# light.net
KiCad netlist of a schematic drawn in EAGLE
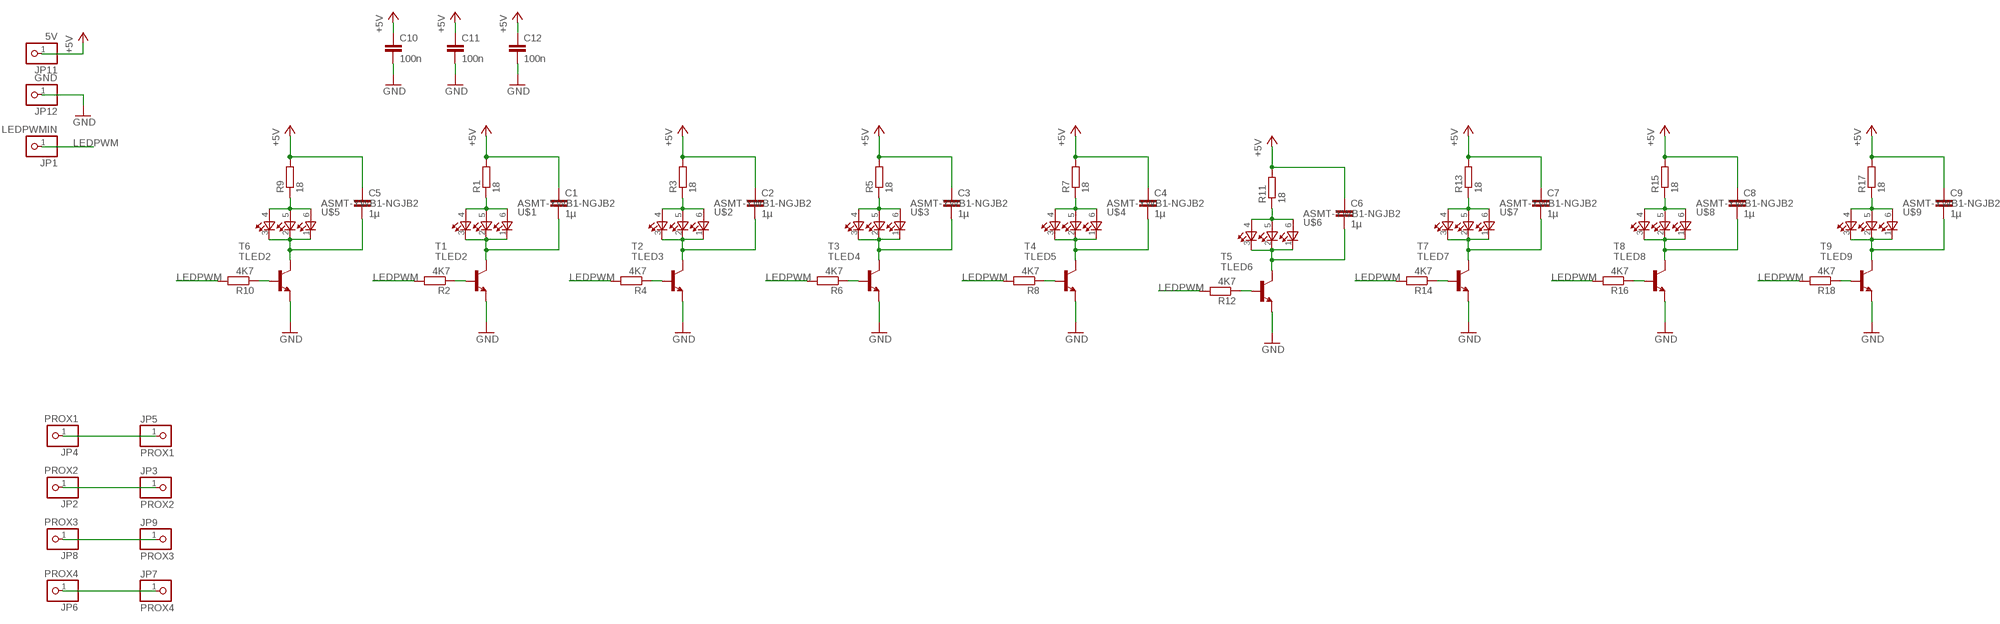
[diagram p0: schematic, sheet 1]

(export (version "E")
  (design (tool "Eeschema 10.0.6"))
  (components
    (comp (ref "C1")
      (value "1µ")
      (footprint "eagle-import:C0805")
      (libsource (lib "eagle-import") (part "C-EUC0805"))
    )
    (comp (ref "C2")
      (value "1µ")
      (footprint "eagle-import:C0805")
      (libsource (lib "eagle-import") (part "C-EUC0805"))
    )
    (comp (ref "C3")
      (value "1µ")
      (footprint "eagle-import:C0805")
      (libsource (lib "eagle-import") (part "C-EUC0805"))
    )
    (comp (ref "C4")
      (value "1µ")
      (footprint "eagle-import:C0805")
      (libsource (lib "eagle-import") (part "C-EUC0805"))
    )
    (comp (ref "C5")
      (value "1µ")
      (footprint "eagle-import:C0805")
      (libsource (lib "eagle-import") (part "C-EUC0805"))
    )
    (comp (ref "C6")
      (value "1µ")
      (footprint "eagle-import:C0805")
      (libsource (lib "eagle-import") (part "C-EUC0805"))
    )
    (comp (ref "C7")
      (value "1µ")
      (footprint "eagle-import:C0805")
      (libsource (lib "eagle-import") (part "C-EUC0805"))
    )
    (comp (ref "C8")
      (value "1µ")
      (footprint "eagle-import:C0805")
      (libsource (lib "eagle-import") (part "C-EUC0805"))
    )
    (comp (ref "C9")
      (value "1µ")
      (footprint "eagle-import:C0805")
      (libsource (lib "eagle-import") (part "C-EUC0805"))
    )
    (comp (ref "C10")
      (value "100n")
      (footprint "eagle-import:C0805")
      (libsource (lib "eagle-import") (part "C-EUC0805"))
    )
    (comp (ref "C11")
      (value "100n")
      (footprint "eagle-import:C0805")
      (libsource (lib "eagle-import") (part "C-EUC0805"))
    )
    (comp (ref "C12")
      (value "100n")
      (footprint "eagle-import:C0805")
      (libsource (lib "eagle-import") (part "C-EUC0805"))
    )
    (comp (ref "JP1")
      (value "LEDPWMIN")
      (footprint "eagle-import:1X01")
      (libsource (lib "eagle-import") (part "PINHD-1X1"))
    )
    (comp (ref "JP2")
      (value "PROX2")
      (footprint "eagle-import:1X01")
      (libsource (lib "eagle-import") (part "PINHD-1X1"))
    )
    (comp (ref "JP3")
      (value "PROX2")
      (footprint "eagle-import:1X01")
      (libsource (lib "eagle-import") (part "PINHD-1X1"))
    )
    (comp (ref "JP4")
      (value "PROX1")
      (footprint "eagle-import:1X01")
      (libsource (lib "eagle-import") (part "PINHD-1X1"))
    )
    (comp (ref "JP5")
      (value "PROX1")
      (footprint "eagle-import:1X01")
      (libsource (lib "eagle-import") (part "PINHD-1X1"))
    )
    (comp (ref "JP6")
      (value "PROX4")
      (footprint "eagle-import:1X01")
      (libsource (lib "eagle-import") (part "PINHD-1X1"))
    )
    (comp (ref "JP7")
      (value "PROX4")
      (footprint "eagle-import:1X01")
      (libsource (lib "eagle-import") (part "PINHD-1X1"))
    )
    (comp (ref "JP8")
      (value "PROX3")
      (footprint "eagle-import:1X01")
      (libsource (lib "eagle-import") (part "PINHD-1X1"))
    )
    (comp (ref "JP9")
      (value "PROX3")
      (footprint "eagle-import:1X01")
      (libsource (lib "eagle-import") (part "PINHD-1X1"))
    )
    (comp (ref "JP11")
      (value "5V")
      (footprint "eagle-import:1X01")
      (libsource (lib "eagle-import") (part "PINHD-1X1"))
    )
    (comp (ref "JP12")
      (value "GND")
      (footprint "eagle-import:1X01")
      (libsource (lib "eagle-import") (part "PINHD-1X1"))
    )
    (comp (ref "R1")
      (value "18")
      (footprint "eagle-import:R0805")
      (libsource (lib "eagle-import") (part "R-EU_R0805"))
    )
    (comp (ref "R2")
      (value "4K7")
      (footprint "eagle-import:R0805")
      (libsource (lib "eagle-import") (part "R-EU_R0805"))
    )
    (comp (ref "R3")
      (value "18")
      (footprint "eagle-import:R0805")
      (libsource (lib "eagle-import") (part "R-EU_R0805"))
    )
    (comp (ref "R4")
      (value "4K7")
      (footprint "eagle-import:R0805")
      (libsource (lib "eagle-import") (part "R-EU_R0805"))
    )
    (comp (ref "R5")
      (value "18")
      (footprint "eagle-import:R0805")
      (libsource (lib "eagle-import") (part "R-EU_R0805"))
    )
    (comp (ref "R6")
      (value "4K7")
      (footprint "eagle-import:R0805")
      (libsource (lib "eagle-import") (part "R-EU_R0805"))
    )
    (comp (ref "R7")
      (value "18")
      (footprint "eagle-import:R0805")
      (libsource (lib "eagle-import") (part "R-EU_R0805"))
    )
    (comp (ref "R8")
      (value "4K7")
      (footprint "eagle-import:R0805")
      (libsource (lib "eagle-import") (part "R-EU_R0805"))
    )
    (comp (ref "R9")
      (value "18")
      (footprint "eagle-import:R0805")
      (libsource (lib "eagle-import") (part "R-EU_R0805"))
    )
    (comp (ref "R10")
      (value "4K7")
      (footprint "eagle-import:R0805")
      (libsource (lib "eagle-import") (part "R-EU_R0805"))
    )
    (comp (ref "R11")
      (value "18")
      (footprint "eagle-import:R0805")
      (libsource (lib "eagle-import") (part "R-EU_R0805"))
    )
    (comp (ref "R12")
      (value "4K7")
      (footprint "eagle-import:R0805")
      (libsource (lib "eagle-import") (part "R-EU_R0805"))
    )
    (comp (ref "R13")
      (value "18")
      (footprint "eagle-import:R0805")
      (libsource (lib "eagle-import") (part "R-EU_R0805"))
    )
    (comp (ref "R14")
      (value "4K7")
      (footprint "eagle-import:R0805")
      (libsource (lib "eagle-import") (part "R-EU_R0805"))
    )
    (comp (ref "R15")
      (value "18")
      (footprint "eagle-import:R0805")
      (libsource (lib "eagle-import") (part "R-EU_R0805"))
    )
    (comp (ref "R16")
      (value "4K7")
      (footprint "eagle-import:R0805")
      (libsource (lib "eagle-import") (part "R-EU_R0805"))
    )
    (comp (ref "R17")
      (value "18")
      (footprint "eagle-import:R0805")
      (libsource (lib "eagle-import") (part "R-EU_R0805"))
    )
    (comp (ref "R18")
      (value "4K7")
      (footprint "eagle-import:R0805")
      (libsource (lib "eagle-import") (part "R-EU_R0805"))
    )
    (comp (ref "T1")
      (value "TLED2")
      (footprint "eagle-import:SOT23-BEC")
      (libsource (lib "eagle-import") (part "-NPN-SOT23-BECMMBT3904LT1"))
    )
    (comp (ref "T2")
      (value "TLED3")
      (footprint "eagle-import:SOT23-BEC")
      (libsource (lib "eagle-import") (part "-NPN-SOT23-BECMMBT3904LT1"))
    )
    (comp (ref "T3")
      (value "TLED4")
      (footprint "eagle-import:SOT23-BEC")
      (libsource (lib "eagle-import") (part "-NPN-SOT23-BECMMBT3904LT1"))
    )
    (comp (ref "T4")
      (value "TLED5")
      (footprint "eagle-import:SOT23-BEC")
      (libsource (lib "eagle-import") (part "-NPN-SOT23-BECMMBT3904LT1"))
    )
    (comp (ref "T5")
      (value "TLED6")
      (footprint "eagle-import:SOT23-BEC")
      (libsource (lib "eagle-import") (part "-NPN-SOT23-BECMMBT3904LT1"))
    )
    (comp (ref "T6")
      (value "TLED2")
      (footprint "eagle-import:SOT23-BEC")
      (libsource (lib "eagle-import") (part "-NPN-SOT23-BECMMBT3904LT1"))
    )
    (comp (ref "T7")
      (value "TLED7")
      (footprint "eagle-import:SOT23-BEC")
      (libsource (lib "eagle-import") (part "-NPN-SOT23-BECMMBT3904LT1"))
    )
    (comp (ref "T8")
      (value "TLED8")
      (footprint "eagle-import:SOT23-BEC")
      (libsource (lib "eagle-import") (part "-NPN-SOT23-BECMMBT3904LT1"))
    )
    (comp (ref "T9")
      (value "TLED9")
      (footprint "eagle-import:SOT23-BEC")
      (libsource (lib "eagle-import") (part "-NPN-SOT23-BECMMBT3904LT1"))
    )
    (comp (ref "U$1")
      (value "ASMT-YWB1-NGJB2")
      (footprint "eagle-import:ASMT-YWB1-NGJB2")
      (libsource (lib "eagle-import") (part "ASMT-YWB1-NGJB2"))
    )
    (comp (ref "U$2")
      (value "ASMT-YWB1-NGJB2")
      (footprint "eagle-import:ASMT-YWB1-NGJB2")
      (libsource (lib "eagle-import") (part "ASMT-YWB1-NGJB2"))
    )
    (comp (ref "U$3")
      (value "ASMT-YWB1-NGJB2")
      (footprint "eagle-import:ASMT-YWB1-NGJB2")
      (libsource (lib "eagle-import") (part "ASMT-YWB1-NGJB2"))
    )
    (comp (ref "U$4")
      (value "ASMT-YWB1-NGJB2")
      (footprint "eagle-import:ASMT-YWB1-NGJB2")
      (libsource (lib "eagle-import") (part "ASMT-YWB1-NGJB2"))
    )
    (comp (ref "U$5")
      (value "ASMT-YWB1-NGJB2")
      (footprint "eagle-import:ASMT-YWB1-NGJB2")
      (libsource (lib "eagle-import") (part "ASMT-YWB1-NGJB2"))
    )
    (comp (ref "U$6")
      (value "ASMT-YWB1-NGJB2")
      (footprint "eagle-import:ASMT-YWB1-NGJB2")
      (libsource (lib "eagle-import") (part "ASMT-YWB1-NGJB2"))
    )
    (comp (ref "U$7")
      (value "ASMT-YWB1-NGJB2")
      (footprint "eagle-import:ASMT-YWB1-NGJB2")
      (libsource (lib "eagle-import") (part "ASMT-YWB1-NGJB2"))
    )
    (comp (ref "U$8")
      (value "ASMT-YWB1-NGJB2")
      (footprint "eagle-import:ASMT-YWB1-NGJB2")
      (libsource (lib "eagle-import") (part "ASMT-YWB1-NGJB2"))
    )
    (comp (ref "U$9")
      (value "ASMT-YWB1-NGJB2")
      (footprint "eagle-import:ASMT-YWB1-NGJB2")
      (libsource (lib "eagle-import") (part "ASMT-YWB1-NGJB2"))
    )
  )
  (nets
    (net (code "1") (name "+5V") (class "Default")
      (node (ref "C1") (pin "1") (pinfunction "1_1") (pintype "passive"))
      (node (ref "C10") (pin "1") (pinfunction "1_1") (pintype "passive"))
      (node (ref "C11") (pin "1") (pinfunction "1_1") (pintype "passive"))
      (node (ref "C12") (pin "1") (pinfunction "1_1") (pintype "passive"))
      (node (ref "C2") (pin "1") (pinfunction "1_1") (pintype "passive"))
      (node (ref "C3") (pin "1") (pinfunction "1_1") (pintype "passive"))
      (node (ref "C4") (pin "1") (pinfunction "1_1") (pintype "passive"))
      (node (ref "C5") (pin "1") (pinfunction "1_1") (pintype "passive"))
      (node (ref "C6") (pin "1") (pinfunction "1_1") (pintype "passive"))
      (node (ref "C7") (pin "1") (pinfunction "1_1") (pintype "passive"))
      (node (ref "C8") (pin "1") (pinfunction "1_1") (pintype "passive"))
      (node (ref "C9") (pin "1") (pinfunction "1_1") (pintype "passive"))
      (node (ref "JP11") (pin "1") (pinfunction "1_1") (pintype "passive"))
      (node (ref "R1") (pin "2") (pinfunction "2_2") (pintype "passive"))
      (node (ref "R11") (pin "2") (pinfunction "2_2") (pintype "passive"))
      (node (ref "R13") (pin "2") (pinfunction "2_2") (pintype "passive"))
      (node (ref "R15") (pin "2") (pinfunction "2_2") (pintype "passive"))
      (node (ref "R17") (pin "2") (pinfunction "2_2") (pintype "passive"))
      (node (ref "R3") (pin "2") (pinfunction "2_2") (pintype "passive"))
      (node (ref "R5") (pin "2") (pinfunction "2_2") (pintype "passive"))
      (node (ref "R7") (pin "2") (pinfunction "2_2") (pintype "passive"))
      (node (ref "R9") (pin "2") (pinfunction "2_2") (pintype "passive"))
    )
    (net (code "2") (name "/LEDPWM") (class "Default")
      (node (ref "JP1") (pin "1") (pinfunction "1_1") (pintype "passive"))
      (node (ref "R10") (pin "2") (pinfunction "2_2") (pintype "passive"))
      (node (ref "R12") (pin "2") (pinfunction "2_2") (pintype "passive"))
      (node (ref "R14") (pin "2") (pinfunction "2_2") (pintype "passive"))
      (node (ref "R16") (pin "2") (pinfunction "2_2") (pintype "passive"))
      (node (ref "R18") (pin "2") (pinfunction "2_2") (pintype "passive"))
      (node (ref "R2") (pin "2") (pinfunction "2_2") (pintype "passive"))
      (node (ref "R4") (pin "2") (pinfunction "2_2") (pintype "passive"))
      (node (ref "R6") (pin "2") (pinfunction "2_2") (pintype "passive"))
      (node (ref "R8") (pin "2") (pinfunction "2_2") (pintype "passive"))
    )
    (net (code "3") (name "GND") (class "Default")
      (node (ref "C10") (pin "2") (pinfunction "2_2") (pintype "passive"))
      (node (ref "C11") (pin "2") (pinfunction "2_2") (pintype "passive"))
      (node (ref "C12") (pin "2") (pinfunction "2_2") (pintype "passive"))
      (node (ref "JP12") (pin "1") (pinfunction "1_1") (pintype "passive"))
      (node (ref "T1") (pin "E") (pinfunction "E_E") (pintype "passive"))
      (node (ref "T2") (pin "E") (pinfunction "E_E") (pintype "passive"))
      (node (ref "T3") (pin "E") (pinfunction "E_E") (pintype "passive"))
      (node (ref "T4") (pin "E") (pinfunction "E_E") (pintype "passive"))
      (node (ref "T5") (pin "E") (pinfunction "E_E") (pintype "passive"))
      (node (ref "T6") (pin "E") (pinfunction "E_E") (pintype "passive"))
      (node (ref "T7") (pin "E") (pinfunction "E_E") (pintype "passive"))
      (node (ref "T8") (pin "E") (pinfunction "E_E") (pintype "passive"))
      (node (ref "T9") (pin "E") (pinfunction "E_E") (pintype "passive"))
    )
    (net (code "4") (name "Net-(C1-Pad2)") (class "Default")
      (node (ref "C1") (pin "2") (pinfunction "2_2") (pintype "passive"))
      (node (ref "T1") (pin "C") (pinfunction "C_C") (pintype "passive"))
      (node (ref "U$1") (pin "1") (pinfunction "1_1") (pintype "passive"))
      (node (ref "U$1") (pin "2") (pinfunction "2_2") (pintype "passive"))
      (node (ref "U$1") (pin "3") (pinfunction "3_3") (pintype "passive"))
    )
    (net (code "5") (name "Net-(C2-Pad2)") (class "Default")
      (node (ref "C2") (pin "2") (pinfunction "2_2") (pintype "passive"))
      (node (ref "T2") (pin "C") (pinfunction "C_C") (pintype "passive"))
      (node (ref "U$2") (pin "1") (pinfunction "1_1") (pintype "passive"))
      (node (ref "U$2") (pin "2") (pinfunction "2_2") (pintype "passive"))
      (node (ref "U$2") (pin "3") (pinfunction "3_3") (pintype "passive"))
    )
    (net (code "6") (name "Net-(C3-Pad2)") (class "Default")
      (node (ref "C3") (pin "2") (pinfunction "2_2") (pintype "passive"))
      (node (ref "T3") (pin "C") (pinfunction "C_C") (pintype "passive"))
      (node (ref "U$3") (pin "1") (pinfunction "1_1") (pintype "passive"))
      (node (ref "U$3") (pin "2") (pinfunction "2_2") (pintype "passive"))
      (node (ref "U$3") (pin "3") (pinfunction "3_3") (pintype "passive"))
    )
    (net (code "7") (name "Net-(C4-Pad2)") (class "Default")
      (node (ref "C4") (pin "2") (pinfunction "2_2") (pintype "passive"))
      (node (ref "T4") (pin "C") (pinfunction "C_C") (pintype "passive"))
      (node (ref "U$4") (pin "1") (pinfunction "1_1") (pintype "passive"))
      (node (ref "U$4") (pin "2") (pinfunction "2_2") (pintype "passive"))
      (node (ref "U$4") (pin "3") (pinfunction "3_3") (pintype "passive"))
    )
    (net (code "8") (name "Net-(C5-Pad2)") (class "Default")
      (node (ref "C5") (pin "2") (pinfunction "2_2") (pintype "passive"))
      (node (ref "T6") (pin "C") (pinfunction "C_C") (pintype "passive"))
      (node (ref "U$5") (pin "1") (pinfunction "1_1") (pintype "passive"))
      (node (ref "U$5") (pin "2") (pinfunction "2_2") (pintype "passive"))
      (node (ref "U$5") (pin "3") (pinfunction "3_3") (pintype "passive"))
    )
    (net (code "9") (name "Net-(C6-Pad2)") (class "Default")
      (node (ref "C6") (pin "2") (pinfunction "2_2") (pintype "passive"))
      (node (ref "T5") (pin "C") (pinfunction "C_C") (pintype "passive"))
      (node (ref "U$6") (pin "1") (pinfunction "1_1") (pintype "passive"))
      (node (ref "U$6") (pin "2") (pinfunction "2_2") (pintype "passive"))
      (node (ref "U$6") (pin "3") (pinfunction "3_3") (pintype "passive"))
    )
    (net (code "10") (name "Net-(C7-Pad2)") (class "Default")
      (node (ref "C7") (pin "2") (pinfunction "2_2") (pintype "passive"))
      (node (ref "T7") (pin "C") (pinfunction "C_C") (pintype "passive"))
      (node (ref "U$7") (pin "1") (pinfunction "1_1") (pintype "passive"))
      (node (ref "U$7") (pin "2") (pinfunction "2_2") (pintype "passive"))
      (node (ref "U$7") (pin "3") (pinfunction "3_3") (pintype "passive"))
    )
    (net (code "11") (name "Net-(C8-Pad2)") (class "Default")
      (node (ref "C8") (pin "2") (pinfunction "2_2") (pintype "passive"))
      (node (ref "T8") (pin "C") (pinfunction "C_C") (pintype "passive"))
      (node (ref "U$8") (pin "1") (pinfunction "1_1") (pintype "passive"))
      (node (ref "U$8") (pin "2") (pinfunction "2_2") (pintype "passive"))
      (node (ref "U$8") (pin "3") (pinfunction "3_3") (pintype "passive"))
    )
    (net (code "12") (name "Net-(C9-Pad2)") (class "Default")
      (node (ref "C9") (pin "2") (pinfunction "2_2") (pintype "passive"))
      (node (ref "T9") (pin "C") (pinfunction "C_C") (pintype "passive"))
      (node (ref "U$9") (pin "1") (pinfunction "1_1") (pintype "passive"))
      (node (ref "U$9") (pin "2") (pinfunction "2_2") (pintype "passive"))
      (node (ref "U$9") (pin "3") (pinfunction "3_3") (pintype "passive"))
    )
    (net (code "13") (name "Net-(JP2-Pad1)") (class "Default")
      (node (ref "JP2") (pin "1") (pinfunction "1_1") (pintype "passive"))
      (node (ref "JP3") (pin "1") (pinfunction "1_1") (pintype "passive"))
    )
    (net (code "14") (name "Net-(JP4-Pad1)") (class "Default")
      (node (ref "JP4") (pin "1") (pinfunction "1_1") (pintype "passive"))
      (node (ref "JP5") (pin "1") (pinfunction "1_1") (pintype "passive"))
    )
    (net (code "15") (name "Net-(JP6-Pad1)") (class "Default")
      (node (ref "JP6") (pin "1") (pinfunction "1_1") (pintype "passive"))
      (node (ref "JP7") (pin "1") (pinfunction "1_1") (pintype "passive"))
    )
    (net (code "16") (name "Net-(JP8-Pad1)") (class "Default")
      (node (ref "JP8") (pin "1") (pinfunction "1_1") (pintype "passive"))
      (node (ref "JP9") (pin "1") (pinfunction "1_1") (pintype "passive"))
    )
    (net (code "17") (name "Net-(R1-Pad1)") (class "Default")
      (node (ref "R1") (pin "1") (pinfunction "1_1") (pintype "passive"))
      (node (ref "U$1") (pin "4") (pinfunction "4_4") (pintype "passive"))
      (node (ref "U$1") (pin "5") (pinfunction "5_5") (pintype "passive"))
      (node (ref "U$1") (pin "6") (pinfunction "6_6") (pintype "passive"))
    )
    (net (code "18") (name "Net-(R2-Pad1)") (class "Default")
      (node (ref "R2") (pin "1") (pinfunction "1_1") (pintype "passive"))
      (node (ref "T1") (pin "B") (pinfunction "B_B") (pintype "passive"))
    )
    (net (code "19") (name "Net-(R3-Pad1)") (class "Default")
      (node (ref "R3") (pin "1") (pinfunction "1_1") (pintype "passive"))
      (node (ref "U$2") (pin "4") (pinfunction "4_4") (pintype "passive"))
      (node (ref "U$2") (pin "5") (pinfunction "5_5") (pintype "passive"))
      (node (ref "U$2") (pin "6") (pinfunction "6_6") (pintype "passive"))
    )
    (net (code "20") (name "Net-(R4-Pad1)") (class "Default")
      (node (ref "R4") (pin "1") (pinfunction "1_1") (pintype "passive"))
      (node (ref "T2") (pin "B") (pinfunction "B_B") (pintype "passive"))
    )
    (net (code "21") (name "Net-(R5-Pad1)") (class "Default")
      (node (ref "R5") (pin "1") (pinfunction "1_1") (pintype "passive"))
      (node (ref "U$3") (pin "4") (pinfunction "4_4") (pintype "passive"))
      (node (ref "U$3") (pin "5") (pinfunction "5_5") (pintype "passive"))
      (node (ref "U$3") (pin "6") (pinfunction "6_6") (pintype "passive"))
    )
    (net (code "22") (name "Net-(R6-Pad1)") (class "Default")
      (node (ref "R6") (pin "1") (pinfunction "1_1") (pintype "passive"))
      (node (ref "T3") (pin "B") (pinfunction "B_B") (pintype "passive"))
    )
    (net (code "23") (name "Net-(R7-Pad1)") (class "Default")
      (node (ref "R7") (pin "1") (pinfunction "1_1") (pintype "passive"))
      (node (ref "U$4") (pin "4") (pinfunction "4_4") (pintype "passive"))
      (node (ref "U$4") (pin "5") (pinfunction "5_5") (pintype "passive"))
      (node (ref "U$4") (pin "6") (pinfunction "6_6") (pintype "passive"))
    )
    (net (code "24") (name "Net-(R8-Pad1)") (class "Default")
      (node (ref "R8") (pin "1") (pinfunction "1_1") (pintype "passive"))
      (node (ref "T4") (pin "B") (pinfunction "B_B") (pintype "passive"))
    )
    (net (code "25") (name "Net-(R9-Pad1)") (class "Default")
      (node (ref "R9") (pin "1") (pinfunction "1_1") (pintype "passive"))
      (node (ref "U$5") (pin "4") (pinfunction "4_4") (pintype "passive"))
      (node (ref "U$5") (pin "5") (pinfunction "5_5") (pintype "passive"))
      (node (ref "U$5") (pin "6") (pinfunction "6_6") (pintype "passive"))
    )
    (net (code "26") (name "Net-(R10-Pad1)") (class "Default")
      (node (ref "R10") (pin "1") (pinfunction "1_1") (pintype "passive"))
      (node (ref "T6") (pin "B") (pinfunction "B_B") (pintype "passive"))
    )
    (net (code "27") (name "Net-(R11-Pad1)") (class "Default")
      (node (ref "R11") (pin "1") (pinfunction "1_1") (pintype "passive"))
      (node (ref "U$6") (pin "4") (pinfunction "4_4") (pintype "passive"))
      (node (ref "U$6") (pin "5") (pinfunction "5_5") (pintype "passive"))
      (node (ref "U$6") (pin "6") (pinfunction "6_6") (pintype "passive"))
    )
    (net (code "28") (name "Net-(R12-Pad1)") (class "Default")
      (node (ref "R12") (pin "1") (pinfunction "1_1") (pintype "passive"))
      (node (ref "T5") (pin "B") (pinfunction "B_B") (pintype "passive"))
    )
    (net (code "29") (name "Net-(R13-Pad1)") (class "Default")
      (node (ref "R13") (pin "1") (pinfunction "1_1") (pintype "passive"))
      (node (ref "U$7") (pin "4") (pinfunction "4_4") (pintype "passive"))
      (node (ref "U$7") (pin "5") (pinfunction "5_5") (pintype "passive"))
      (node (ref "U$7") (pin "6") (pinfunction "6_6") (pintype "passive"))
    )
    (net (code "30") (name "Net-(R14-Pad1)") (class "Default")
      (node (ref "R14") (pin "1") (pinfunction "1_1") (pintype "passive"))
      (node (ref "T7") (pin "B") (pinfunction "B_B") (pintype "passive"))
    )
    (net (code "31") (name "Net-(R15-Pad1)") (class "Default")
      (node (ref "R15") (pin "1") (pinfunction "1_1") (pintype "passive"))
      (node (ref "U$8") (pin "4") (pinfunction "4_4") (pintype "passive"))
      (node (ref "U$8") (pin "5") (pinfunction "5_5") (pintype "passive"))
      (node (ref "U$8") (pin "6") (pinfunction "6_6") (pintype "passive"))
    )
    (net (code "32") (name "Net-(R16-Pad1)") (class "Default")
      (node (ref "R16") (pin "1") (pinfunction "1_1") (pintype "passive"))
      (node (ref "T8") (pin "B") (pinfunction "B_B") (pintype "passive"))
    )
    (net (code "33") (name "Net-(R17-Pad1)") (class "Default")
      (node (ref "R17") (pin "1") (pinfunction "1_1") (pintype "passive"))
      (node (ref "U$9") (pin "4") (pinfunction "4_4") (pintype "passive"))
      (node (ref "U$9") (pin "5") (pinfunction "5_5") (pintype "passive"))
      (node (ref "U$9") (pin "6") (pinfunction "6_6") (pintype "passive"))
    )
    (net (code "34") (name "Net-(R18-Pad1)") (class "Default")
      (node (ref "R18") (pin "1") (pinfunction "1_1") (pintype "passive"))
      (node (ref "T9") (pin "B") (pinfunction "B_B") (pintype "passive"))
    )
  )
)
